# 12_TO_3V3_VOLTAGE_DIVIDER.net
KiCad netlist of a schematic drawn in Altium Designer
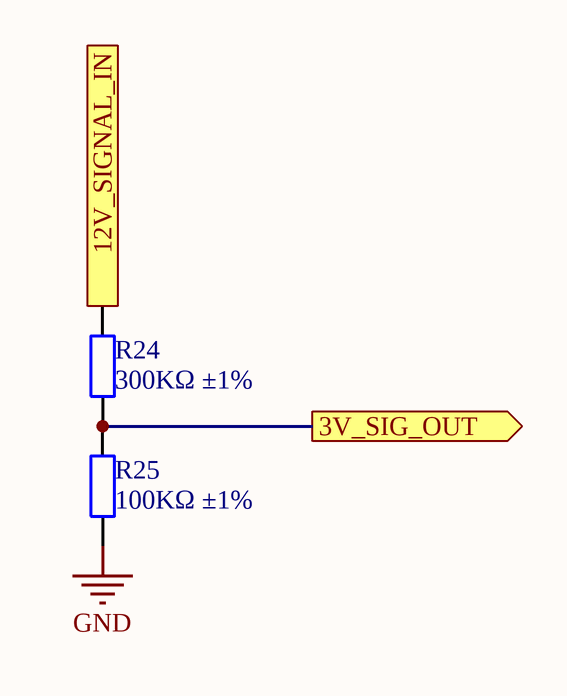
[diagram p0: 12_TO_3V3_VOLTAGE_DIVIDER.SchDoc]

(export (version "E")
  (design (tool "Eeschema 10.0.6"))
  (components
    (comp (ref "R24")
      (value "300KΩ ±1%")
      (footprint "0402_R")
      (description "Chip resistor")
      (fields (field (name "MANUFACTURER") "Uniroyal Elec") (field (name "PARTNUMBER") "0402WGF3003TCE"))
      (libsource (lib "Miscellaneous Devices LC") (part "0402 300K (3003) 1%"))
    )
    (comp (ref "R25")
      (value "100KΩ ±1%")
      (footprint "0402_R")
      (description "Chip resistor")
      (fields (field (name "MANUFACTURER") "Uniroyal Elec") (field (name "PARTNUMBER") "0402WGF1003TCE"))
      (libsource (lib "Miscellaneous Devices LC") (part "0402 100K (1003) 1%"))
    )
  )
  (nets
    (net (code "1") (name "/3V_SIG_OUT") (class "Default")
      (node (ref "R24") (pin "1") (pinfunction "1_1") (pintype "passive"))
      (node (ref "R25") (pin "2") (pinfunction "2_2") (pintype "passive"))
    )
    (net (code "2") (name "/12V_SIGNAL_IN") (class "Default")
      (node (ref "R24") (pin "2") (pinfunction "2_2") (pintype "passive"))
    )
    (net (code "3") (name "GND") (class "Default")
      (node (ref "R25") (pin "1") (pinfunction "1_1") (pintype "passive"))
    )
  )
)
